# stepper_nano.net
KiCad netlist of a schematic drawn in EAGLE
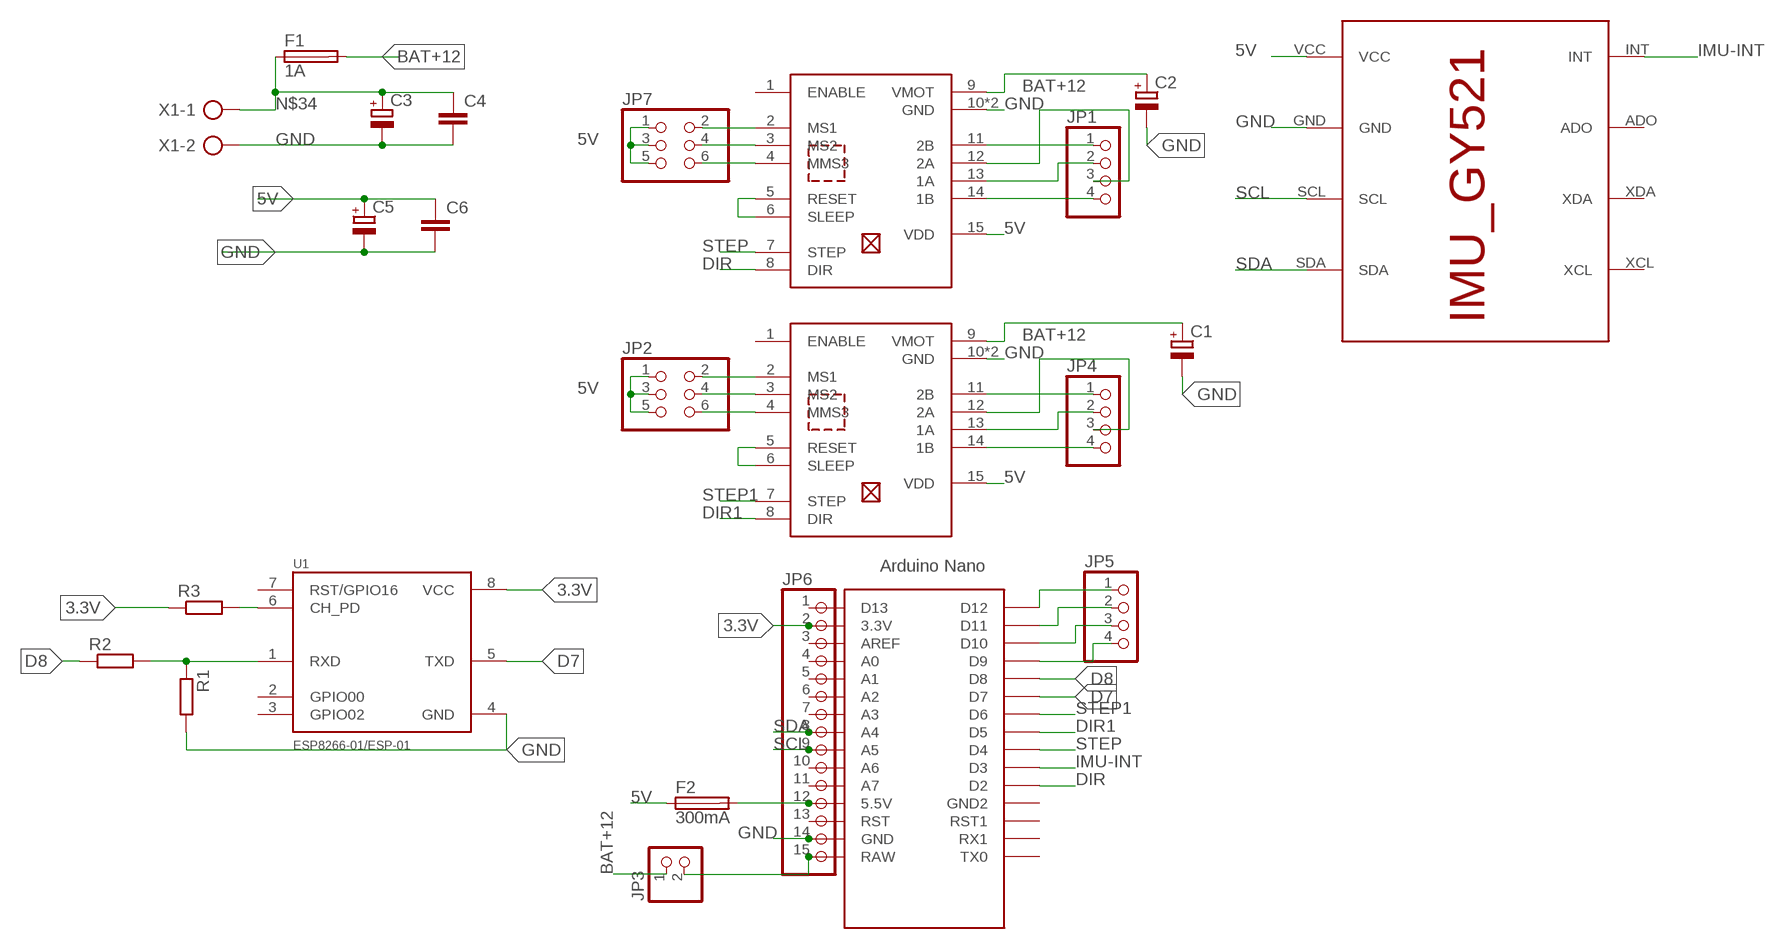
[diagram p0: schematic, sheet 1]

(export (version "E")
  (design (tool "Eeschema 10.0.6"))
  (components
    (comp (ref "C1")
      (value "CPOL-EUE2-5")
      (footprint "eagle-import:E2-5")
      (libsource (lib "eagle-import") (part "CPOL-EUE2-5"))
    )
    (comp (ref "C2")
      (value "CPOL-EUE2-5")
      (footprint "eagle-import:E2-5")
      (libsource (lib "eagle-import") (part "CPOL-EUE2-5"))
    )
    (comp (ref "C3")
      (value "CPOL-EUE2-5")
      (footprint "eagle-import:E2-5")
      (libsource (lib "eagle-import") (part "CPOL-EUE2-5"))
    )
    (comp (ref "C4")
      (value "C-EU025-024X044")
      (footprint "eagle-import:C025-024X044")
      (libsource (lib "eagle-import") (part "C-EU025-024X044"))
    )
    (comp (ref "C5")
      (value "CPOL-EUE2-5")
      (footprint "eagle-import:E2-5")
      (libsource (lib "eagle-import") (part "CPOL-EUE2-5"))
    )
    (comp (ref "C6")
      (value "C-EU025-024X044")
      (footprint "eagle-import:C025-024X044")
      (libsource (lib "eagle-import") (part "C-EU025-024X044"))
    )
    (comp (ref "F1")
      (value "1A")
      (footprint "eagle-import:SH22")
      (libsource (lib "eagle-import") (part "FUSESH22"))
    )
    (comp (ref "F2")
      (value "300mA")
      (footprint "eagle-import:SH22")
      (libsource (lib "eagle-import") (part "FUSESH22"))
    )
    (comp (ref "JP1")
      (value "PINHD-1X4")
      (footprint "eagle-import:1X04")
      (libsource (lib "eagle-import") (part "PINHD-1X4"))
    )
    (comp (ref "JP2")
      (value "PINHD-2X3")
      (footprint "eagle-import:2X03")
      (libsource (lib "eagle-import") (part "PINHD-2X3"))
    )
    (comp (ref "JP3")
      (value "PINHD-1X2")
      (footprint "eagle-import:1X02")
      (libsource (lib "eagle-import") (part "PINHD-1X2"))
    )
    (comp (ref "JP4")
      (value "PINHD-1X4")
      (footprint "eagle-import:1X04")
      (libsource (lib "eagle-import") (part "PINHD-1X4"))
    )
    (comp (ref "JP5")
      (value "PINHD-1X4")
      (footprint "eagle-import:1X04")
      (libsource (lib "eagle-import") (part "PINHD-1X4"))
    )
    (comp (ref "JP6")
      (value "PINHD-1X15")
      (footprint "eagle-import:1X15")
      (libsource (lib "eagle-import") (part "PINHD-1X15"))
    )
    (comp (ref "JP7")
      (value "PINHD-2X3")
      (footprint "eagle-import:2X03")
      (libsource (lib "eagle-import") (part "PINHD-2X3"))
    )
    (comp (ref "R1")
      (value "R-EU_0204/5")
      (footprint "eagle-import:0204_5")
      (libsource (lib "eagle-import") (part "R-EU_0204/5"))
    )
    (comp (ref "R2")
      (value "R-EU_0204/7")
      (footprint "eagle-import:0204_7")
      (libsource (lib "eagle-import") (part "R-EU_0204/7"))
    )
    (comp (ref "R3")
      (value "R-EU_0204/7")
      (footprint "eagle-import:0204_7")
      (libsource (lib "eagle-import") (part "R-EU_0204/7"))
    )
    (comp (ref "U$1")
      (value "ARDUINO_NANO")
      (footprint "eagle-import:NANO")
      (libsource (lib "eagle-import") (part "ARDUINO_NANO"))
    )
    (comp (ref "U$2")
      (value "IMU-MPU")
      (footprint "eagle-import:IMU_GY521")
      (libsource (lib "eagle-import") (part "IMU-MPU"))
    )
    (comp (ref "U$3")
      (value "STEPPER-DRIVER")
      (footprint "eagle-import:A4988-DRIVER")
      (libsource (lib "eagle-import") (part "STEPPER-DRIVER"))
    )
    (comp (ref "U$4")
      (value "STEPPER-DRIVER")
      (footprint "eagle-import:A4988-DRIVER")
      (libsource (lib "eagle-import") (part "STEPPER-DRIVER"))
    )
    (comp (ref "U1")
      (value "ESP8266-01/ESP-01")
      (footprint "eagle-import:XCVR_ESP8266-01_ESP-01")
      (fields (field (name "MF") "AI-Thinker"))
      (libsource (lib "eagle-import") (part "ESP8266-01/ESP-01"))
    )
    (comp (ref "X1")
      (value "AK300/2")
      (footprint "eagle-import:AK300_2")
      (libsource (lib "eagle-import") (part "AK300/2"))
    )
  )
  (nets
    (net (code "1") (name "/DIR") (class "Default")
      (node (ref "U$1") (pin "D2") (pinfunction "D2_D2") (pintype "bidirectional"))
      (node (ref "U$3") (pin "8") (pinfunction "DIR_8") (pintype "bidirectional"))
    )
    (net (code "2") (name "/DIR1") (class "Default")
      (node (ref "U$1") (pin "D5") (pinfunction "D5_D5") (pintype "bidirectional"))
      (node (ref "U$4") (pin "8") (pinfunction "DIR_8") (pintype "bidirectional"))
    )
    (net (code "3") (name "/IMU-INT") (class "Default")
      (node (ref "U$1") (pin "D3") (pinfunction "D3_D3") (pintype "bidirectional"))
      (node (ref "U$2") (pin "INT") (pinfunction "INT_INT") (pintype "bidirectional"))
    )
    (net (code "4") (name "/N$34") (class "Default")
      (node (ref "C3") (pin "+") (pinfunction "+_+") (pintype "passive"))
      (node (ref "C4") (pin "1") (pinfunction "1_1") (pintype "passive"))
      (node (ref "F1") (pin "1") (pinfunction "1_1") (pintype "passive"))
      (node (ref "X1") (pin "1") (pinfunction "KL_1") (pintype "passive"))
    )
    (net (code "5") (name "/SCL") (class "Default")
      (node (ref "JP6") (pin "9") (pinfunction "9_9") (pintype "passive"))
      (node (ref "U$1") (pin "A5") (pinfunction "A5_A5") (pintype "bidirectional"))
      (node (ref "U$2") (pin "SCL") (pinfunction "SCL_SCL") (pintype "bidirectional"))
    )
    (net (code "6") (name "/SDA") (class "Default")
      (node (ref "JP6") (pin "8") (pinfunction "8_8") (pintype "passive"))
      (node (ref "U$1") (pin "A4") (pinfunction "A4_A4") (pintype "bidirectional"))
      (node (ref "U$2") (pin "SDA") (pinfunction "SDA_SDA") (pintype "bidirectional"))
    )
    (net (code "7") (name "/STEP") (class "Default")
      (node (ref "U$1") (pin "D4") (pinfunction "D4_D4") (pintype "bidirectional"))
      (node (ref "U$3") (pin "7") (pinfunction "STEP_7") (pintype "bidirectional"))
    )
    (net (code "8") (name "/STEP1") (class "Default")
      (node (ref "U$1") (pin "D6") (pinfunction "D6_D6") (pintype "bidirectional"))
      (node (ref "U$4") (pin "7") (pinfunction "STEP_7") (pintype "bidirectional"))
    )
    (net (code "9") (name "3.3V") (class "Default")
      (node (ref "JP6") (pin "2") (pinfunction "2_2") (pintype "passive"))
      (node (ref "R3") (pin "1") (pinfunction "1_1") (pintype "passive"))
      (node (ref "U$1") (pin "3.3V") (pinfunction "3.3V_3.3V") (pintype "bidirectional"))
      (node (ref "U1") (pin "8") (pinfunction "VCC_8") (pintype "power_in"))
    )
    (net (code "10") (name "5V") (class "Default")
      (node (ref "C5") (pin "+") (pinfunction "+_+") (pintype "passive"))
      (node (ref "C6") (pin "1") (pinfunction "1_1") (pintype "passive"))
      (node (ref "F2") (pin "1") (pinfunction "1_1") (pintype "passive"))
      (node (ref "JP2") (pin "1") (pinfunction "1_1") (pintype "passive"))
      (node (ref "JP2") (pin "3") (pinfunction "3_3") (pintype "passive"))
      (node (ref "JP2") (pin "5") (pinfunction "5_5") (pintype "passive"))
      (node (ref "JP7") (pin "1") (pinfunction "1_1") (pintype "passive"))
      (node (ref "JP7") (pin "3") (pinfunction "3_3") (pintype "passive"))
      (node (ref "JP7") (pin "5") (pinfunction "5_5") (pintype "passive"))
      (node (ref "U$2") (pin "VCC") (pinfunction "VCC_VCC") (pintype "bidirectional"))
      (node (ref "U$3") (pin "15") (pinfunction "VDD_15") (pintype "bidirectional"))
      (node (ref "U$4") (pin "15") (pinfunction "VDD_15") (pintype "bidirectional"))
    )
    (net (code "11") (name "BAT+12") (class "Default")
      (node (ref "C1") (pin "+") (pinfunction "+_+") (pintype "passive"))
      (node (ref "C2") (pin "+") (pinfunction "+_+") (pintype "passive"))
      (node (ref "F1") (pin "2") (pinfunction "2_2") (pintype "passive"))
      (node (ref "JP3") (pin "1") (pinfunction "1_1") (pintype "passive"))
      (node (ref "U$3") (pin "9") (pinfunction "VMOT_9") (pintype "bidirectional"))
      (node (ref "U$4") (pin "9") (pinfunction "VMOT_9") (pintype "bidirectional"))
    )
    (net (code "12") (name "D7") (class "Default")
      (node (ref "U$1") (pin "D7") (pinfunction "D7_D7") (pintype "bidirectional"))
      (node (ref "U1") (pin "5") (pinfunction "TXD_5") (pintype "output"))
    )
    (net (code "13") (name "D8") (class "Default")
      (node (ref "R2") (pin "1") (pinfunction "1_1") (pintype "passive"))
      (node (ref "U$1") (pin "D8") (pinfunction "D8_D8") (pintype "bidirectional"))
    )
    (net (code "14") (name "GND") (class "Default")
      (node (ref "C1") (pin "-") (pinfunction "-_-") (pintype "passive"))
      (node (ref "C2") (pin "-") (pinfunction "-_-") (pintype "passive"))
      (node (ref "C3") (pin "-") (pinfunction "-_-") (pintype "passive"))
      (node (ref "C4") (pin "2") (pinfunction "2_2") (pintype "passive"))
      (node (ref "C5") (pin "-") (pinfunction "-_-") (pintype "passive"))
      (node (ref "C6") (pin "2") (pinfunction "2_2") (pintype "passive"))
      (node (ref "JP6") (pin "14") (pinfunction "14_14") (pintype "passive"))
      (node (ref "R1") (pin "2") (pinfunction "2_2") (pintype "passive"))
      (node (ref "U$1") (pin "GND") (pinfunction "GND_GND") (pintype "bidirectional"))
      (node (ref "U$2") (pin "GND") (pinfunction "GND_GND") (pintype "bidirectional"))
      (node (ref "U$3") (pin "10") (pinfunction "GND_10") (pintype "bidirectional"))
      (node (ref "U$3") (pin "16") (pinfunction "GND_16") (pintype "bidirectional"))
      (node (ref "U$4") (pin "10") (pinfunction "GND_10") (pintype "bidirectional"))
      (node (ref "U$4") (pin "16") (pinfunction "GND_16") (pintype "bidirectional"))
      (node (ref "U1") (pin "4") (pinfunction "GND_4") (pintype "power_in"))
      (node (ref "X1") (pin "2") (pinfunction "KL_2") (pintype "passive"))
    )
    (net (code "15") (name "Net-(JP3-Pad2)") (class "Default")
      (node (ref "JP3") (pin "2") (pinfunction "2_2") (pintype "passive"))
      (node (ref "JP6") (pin "15") (pinfunction "15_15") (pintype "passive"))
      (node (ref "U$1") (pin "RAW") (pinfunction "RAW_RAW") (pintype "bidirectional"))
    )
    (net (code "16") (name "Net-(JP5-Pad1)") (class "Default")
      (node (ref "JP5") (pin "1") (pinfunction "1_1") (pintype "passive"))
      (node (ref "U$1") (pin "D12") (pinfunction "D12_D12") (pintype "bidirectional"))
    )
    (net (code "17") (name "Net-(JP5-Pad2)") (class "Default")
      (node (ref "JP5") (pin "2") (pinfunction "2_2") (pintype "passive"))
      (node (ref "U$1") (pin "D11") (pinfunction "D11_D11") (pintype "bidirectional"))
    )
    (net (code "18") (name "Net-(JP5-Pad3)") (class "Default")
      (node (ref "JP5") (pin "3") (pinfunction "3_3") (pintype "passive"))
      (node (ref "U$1") (pin "D10") (pinfunction "D10_D10") (pintype "bidirectional"))
    )
    (net (code "19") (name "Net-(JP5-Pad4)") (class "Default")
      (node (ref "JP5") (pin "4") (pinfunction "4_4") (pintype "passive"))
      (node (ref "U$1") (pin "D9") (pinfunction "D9_D9") (pintype "bidirectional"))
    )
    (net (code "20") (name "Net-(JP6-Pad1)") (class "Default")
      (node (ref "JP6") (pin "1") (pinfunction "1_1") (pintype "passive"))
      (node (ref "U$1") (pin "D13") (pinfunction "D13_D13") (pintype "bidirectional"))
    )
    (net (code "21") (name "Net-(JP6-Pad3)") (class "Default")
      (node (ref "JP6") (pin "3") (pinfunction "3_3") (pintype "passive"))
      (node (ref "U$1") (pin "AREF") (pinfunction "AREF_AREF") (pintype "bidirectional"))
    )
    (net (code "22") (name "Net-(JP6-Pad4)") (class "Default")
      (node (ref "JP6") (pin "4") (pinfunction "4_4") (pintype "passive"))
      (node (ref "U$1") (pin "A0") (pinfunction "A0_A0") (pintype "bidirectional"))
    )
    (net (code "23") (name "Net-(JP6-Pad5)") (class "Default")
      (node (ref "JP6") (pin "5") (pinfunction "5_5") (pintype "passive"))
      (node (ref "U$1") (pin "A1") (pinfunction "A1_A1") (pintype "bidirectional"))
    )
    (net (code "24") (name "Net-(JP6-Pad6)") (class "Default")
      (node (ref "JP6") (pin "6") (pinfunction "6_6") (pintype "passive"))
      (node (ref "U$1") (pin "A2") (pinfunction "A2_A2") (pintype "bidirectional"))
    )
    (net (code "25") (name "Net-(JP6-Pad7)") (class "Default")
      (node (ref "JP6") (pin "7") (pinfunction "7_7") (pintype "passive"))
      (node (ref "U$1") (pin "A3") (pinfunction "A3_A3") (pintype "bidirectional"))
    )
    (net (code "26") (name "Net-(JP6-Pad10)") (class "Default")
      (node (ref "JP6") (pin "10") (pinfunction "10_10") (pintype "passive"))
      (node (ref "U$1") (pin "A6") (pinfunction "A6_A6") (pintype "bidirectional"))
    )
    (net (code "27") (name "Net-(JP6-Pad11)") (class "Default")
      (node (ref "JP6") (pin "11") (pinfunction "11_11") (pintype "passive"))
      (node (ref "U$1") (pin "A7") (pinfunction "A7_A7") (pintype "bidirectional"))
    )
    (net (code "28") (name "Net-(JP6-Pad13)") (class "Default")
      (node (ref "JP6") (pin "13") (pinfunction "13_13") (pintype "passive"))
      (node (ref "U$1") (pin "RST") (pinfunction "RST_RST") (pintype "bidirectional"))
    )
    (net (code "29") (name "Net-(U$1-5.5V)") (class "Default")
      (node (ref "F2") (pin "2") (pinfunction "2_2") (pintype "passive"))
      (node (ref "JP6") (pin "12") (pinfunction "12_12") (pintype "passive"))
      (node (ref "U$1") (pin "5V") (pinfunction "5.5V_5V") (pintype "bidirectional"))
    )
    (net (code "30") (name "Net-(U$3-1A)") (class "Default")
      (node (ref "JP1") (pin "2") (pinfunction "2_2") (pintype "passive"))
      (node (ref "U$3") (pin "13") (pinfunction "1A_13") (pintype "bidirectional"))
    )
    (net (code "31") (name "Net-(U$3-1B)") (class "Default")
      (node (ref "JP1") (pin "4") (pinfunction "4_4") (pintype "passive"))
      (node (ref "U$3") (pin "14") (pinfunction "1B_14") (pintype "bidirectional"))
    )
    (net (code "32") (name "Net-(U$3-2A)") (class "Default")
      (node (ref "JP1") (pin "3") (pinfunction "3_3") (pintype "passive"))
      (node (ref "U$3") (pin "12") (pinfunction "2A_12") (pintype "bidirectional"))
    )
    (net (code "33") (name "Net-(U$3-2B)") (class "Default")
      (node (ref "JP1") (pin "1") (pinfunction "1_1") (pintype "passive"))
      (node (ref "U$3") (pin "11") (pinfunction "2B_11") (pintype "bidirectional"))
    )
    (net (code "34") (name "Net-(U$3-MMS3)") (class "Default")
      (node (ref "JP7") (pin "6") (pinfunction "6_6") (pintype "passive"))
      (node (ref "U$3") (pin "4") (pinfunction "MMS3_4") (pintype "bidirectional"))
    )
    (net (code "35") (name "Net-(U$3-MS1)") (class "Default")
      (node (ref "JP7") (pin "2") (pinfunction "2_2") (pintype "passive"))
      (node (ref "U$3") (pin "2") (pinfunction "MS1_2") (pintype "bidirectional"))
    )
    (net (code "36") (name "Net-(U$3-MS2)") (class "Default")
      (node (ref "JP7") (pin "4") (pinfunction "4_4") (pintype "passive"))
      (node (ref "U$3") (pin "3") (pinfunction "MS2_3") (pintype "bidirectional"))
    )
    (net (code "37") (name "Net-(U$3-RESET)") (class "Default")
      (node (ref "U$3") (pin "5") (pinfunction "RESET_5") (pintype "bidirectional"))
      (node (ref "U$3") (pin "6") (pinfunction "SLEEP_6") (pintype "bidirectional"))
    )
    (net (code "38") (name "Net-(U$4-1A)") (class "Default")
      (node (ref "JP4") (pin "2") (pinfunction "2_2") (pintype "passive"))
      (node (ref "U$4") (pin "13") (pinfunction "1A_13") (pintype "bidirectional"))
    )
    (net (code "39") (name "Net-(U$4-1B)") (class "Default")
      (node (ref "JP4") (pin "4") (pinfunction "4_4") (pintype "passive"))
      (node (ref "U$4") (pin "14") (pinfunction "1B_14") (pintype "bidirectional"))
    )
    (net (code "40") (name "Net-(U$4-2A)") (class "Default")
      (node (ref "JP4") (pin "3") (pinfunction "3_3") (pintype "passive"))
      (node (ref "U$4") (pin "12") (pinfunction "2A_12") (pintype "bidirectional"))
    )
    (net (code "41") (name "Net-(U$4-2B)") (class "Default")
      (node (ref "JP4") (pin "1") (pinfunction "1_1") (pintype "passive"))
      (node (ref "U$4") (pin "11") (pinfunction "2B_11") (pintype "bidirectional"))
    )
    (net (code "42") (name "Net-(U$4-MMS3)") (class "Default")
      (node (ref "JP2") (pin "6") (pinfunction "6_6") (pintype "passive"))
      (node (ref "U$4") (pin "4") (pinfunction "MMS3_4") (pintype "bidirectional"))
    )
    (net (code "43") (name "Net-(U$4-MS1)") (class "Default")
      (node (ref "JP2") (pin "2") (pinfunction "2_2") (pintype "passive"))
      (node (ref "U$4") (pin "2") (pinfunction "MS1_2") (pintype "bidirectional"))
    )
    (net (code "44") (name "Net-(U$4-MS2)") (class "Default")
      (node (ref "JP2") (pin "4") (pinfunction "4_4") (pintype "passive"))
      (node (ref "U$4") (pin "3") (pinfunction "MS2_3") (pintype "bidirectional"))
    )
    (net (code "45") (name "Net-(U$4-RESET)") (class "Default")
      (node (ref "U$4") (pin "5") (pinfunction "RESET_5") (pintype "bidirectional"))
      (node (ref "U$4") (pin "6") (pinfunction "SLEEP_6") (pintype "bidirectional"))
    )
    (net (code "46") (name "Net-(U1-CH_PD)") (class "Default")
      (node (ref "R3") (pin "2") (pinfunction "2_2") (pintype "passive"))
      (node (ref "U1") (pin "6") (pinfunction "CH_PD_6") (pintype "input"))
    )
    (net (code "47") (name "Net-(U1-RXD)") (class "Default")
      (node (ref "R1") (pin "1") (pinfunction "1_1") (pintype "passive"))
      (node (ref "R2") (pin "2") (pinfunction "2_2") (pintype "passive"))
      (node (ref "U1") (pin "1") (pinfunction "RXD_1") (pintype "input"))
    )
    (net (code "48") (name "unconnected-(U$1-GND2-PadGND1)") (class "Default")
      (node (ref "U$1") (pin "GND1") (pinfunction "GND2_GND1") (pintype "bidirectional"))
    )
    (net (code "49") (name "unconnected-(U$1-PadRST1)") (class "Default")
      (node (ref "U$1") (pin "RST1") (pinfunction "RST1_RST1") (pintype "bidirectional"))
    )
    (net (code "50") (name "unconnected-(U$1-PadRX1)") (class "Default")
      (node (ref "U$1") (pin "RX1") (pinfunction "RX1_RX1") (pintype "bidirectional"))
    )
    (net (code "51") (name "unconnected-(U$1-PadTX0)") (class "Default")
      (node (ref "U$1") (pin "TX0") (pinfunction "TX0_TX0") (pintype "bidirectional"))
    )
    (net (code "52") (name "unconnected-(U$2-PadADO)") (class "Default")
      (node (ref "U$2") (pin "ADO") (pinfunction "ADO_ADO") (pintype "bidirectional"))
    )
    (net (code "53") (name "unconnected-(U$2-PadXCL)") (class "Default")
      (node (ref "U$2") (pin "XCL") (pinfunction "XCL_XCL") (pintype "bidirectional"))
    )
    (net (code "54") (name "unconnected-(U$2-PadXDA)") (class "Default")
      (node (ref "U$2") (pin "XDA") (pinfunction "XDA_XDA") (pintype "bidirectional"))
    )
    (net (code "55") (name "unconnected-(U$3-ENABLE-Pad1)") (class "Default")
      (node (ref "U$3") (pin "1") (pinfunction "ENABLE_1") (pintype "bidirectional"))
    )
    (net (code "56") (name "unconnected-(U$4-ENABLE-Pad1)") (class "Default")
      (node (ref "U$4") (pin "1") (pinfunction "ENABLE_1") (pintype "bidirectional"))
    )
    (net (code "57") (name "unconnected-(U1-GPIO00-Pad2)") (class "Default")
      (node (ref "U1") (pin "2") (pinfunction "GPIO00_2") (pintype "bidirectional"))
    )
    (net (code "58") (name "unconnected-(U1-GPIO02-Pad3)") (class "Default")
      (node (ref "U1") (pin "3") (pinfunction "GPIO02_3") (pintype "bidirectional"))
    )
    (net (code "59") (name "unconnected-(U1-RST{slash}GPIO16-Pad7)") (class "Default")
      (node (ref "U1") (pin "7") (pinfunction "RST/GPIO16_7") (pintype "input"))
    )
  )
)
